# imu.net
KiCad netlist of a schematic drawn in Altium Designer
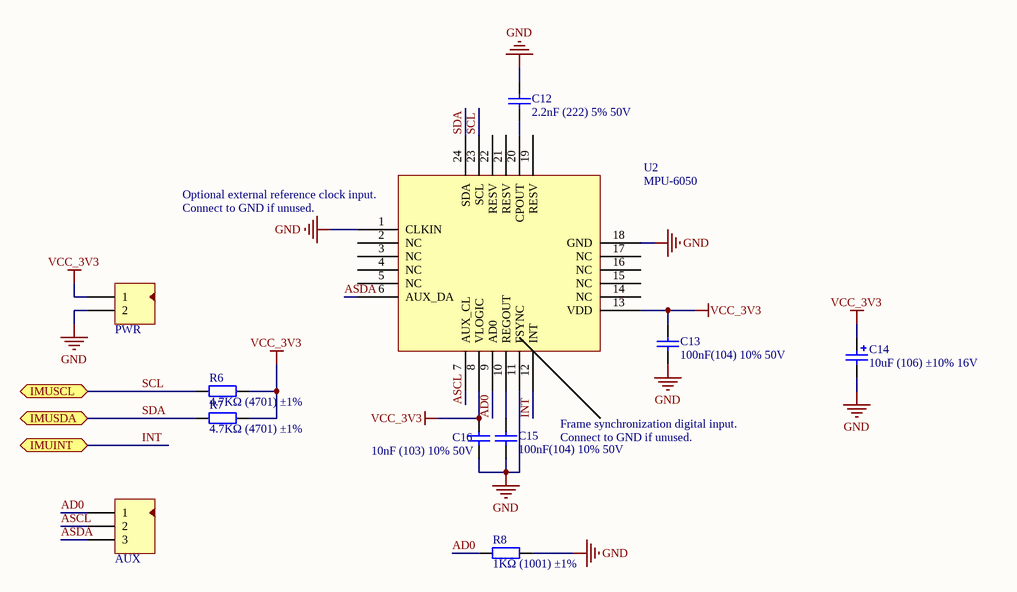
[diagram p0: imu.SchDoc]

(export (version "E")
  (design (tool "Eeschema 10.0.6"))
  (components
    (comp (ref "C12")
      (value "2.2nF (222) 5% 50V")
      (footprint "LC-0805_C")
      (description "贴片电容")
      (libsource (lib "Miscellaneous Devices LC") (part "0805 2.2nF (222) 5% 50V"))
    )
    (comp (ref "C13")
      (value "100nF(104) 10% 50V")
      (footprint "LC-0805_C")
      (description "贴片电容")
      (libsource (lib "Miscellaneous Devices LC") (part "0805 100nF(104) 10% 50V"))
    )
    (comp (ref "C14")
      (value "10uF (106) ±10% 16V")
      (footprint "LC-CASE-A_3216")
      (description "钽电容")
      (libsource (lib "Miscellaneous Devices LC") (part "3216 10uF (106) 10% 16V"))
    )
    (comp (ref "C15")
      (value "100nF(104) 10% 50V")
      (footprint "LC-0805_C")
      (description "贴片电容")
      (libsource (lib "Miscellaneous Devices LC") (part "0805 100nF(104) 10% 50V"))
    )
    (comp (ref "C16")
      (value "10nF (103) 10% 50V")
      (footprint "LC-0805_C")
      (description "贴片电容")
      (libsource (lib "Miscellaneous Devices LC") (part "0805 10nF (103) 10% 50V"))
    )
    (comp (ref "P6")
      (value "PWR")
      (footprint "HDR2X1-2.54")
      (description "接插件")
      (fields (field (name "PUBLISHER") "Altium Limited"))
      (libsource (lib "HDR_Fszhang") (part "Header 2"))
    )
    (comp (ref "P7")
      (value "AUX")
      (footprint "HDR3X1-2.54")
      (description "接插件")
      (fields (field (name "PUBLISHER") "Altium Limited"))
      (libsource (lib "HDR_Fszhang") (part "Header 3"))
    )
    (comp (ref "R6")
      (value "4.7KΩ (4701) ±1%")
      (footprint "LC-0805_R")
      (description "贴片电阻")
      (libsource (lib "Miscellaneous Devices LC") (part "0805 4.7KΩ (4701) 1%"))
    )
    (comp (ref "R7")
      (value "4.7KΩ (4701) ±1%")
      (footprint "LC-0805_R")
      (description "贴片电阻")
      (libsource (lib "Miscellaneous Devices LC") (part "0805 4.7KΩ (4701) 1%"))
    )
    (comp (ref "R8")
      (value "1KΩ (1001) ±1%")
      (footprint "LC-0805_R")
      (description "贴片电阻")
      (libsource (lib "Miscellaneous Devices LC") (part "0805 1KΩ (1001) 1%"))
    )
    (comp (ref "U2")
      (value "MPU-6050")
      (footprint "LC-QFN-24_4x4x05P")
      (description "传感器")
      (libsource (lib "Miscellaneous Devices LC") (part "MPU-6050"))
    )
  )
  (nets
    (net (code "1") (name "/AD0") (class "Default")
      (node (ref "P7") (pin "1") (pinfunction "1_1") (pintype "passive"))
      (node (ref "R8") (pin "1") (pinfunction "1_1") (pintype "passive"))
      (node (ref "U2") (pin "9") (pinfunction "AD0_9") (pintype "passive"))
    )
    (net (code "2") (name "/ASCL") (class "Default")
      (node (ref "P7") (pin "2") (pinfunction "2_2") (pintype "passive"))
      (node (ref "U2") (pin "7") (pinfunction "AUX_CL_7") (pintype "passive"))
    )
    (net (code "3") (name "/ASDA") (class "Default")
      (node (ref "P7") (pin "3") (pinfunction "3_3") (pintype "passive"))
      (node (ref "U2") (pin "6") (pinfunction "AUX_DA_6") (pintype "passive"))
    )
    (net (code "4") (name "/INT") (class "Default")
      (node (ref "U2") (pin "12") (pinfunction "INT_12") (pintype "passive"))
    )
    (net (code "5") (name "/SCL") (class "Default")
      (node (ref "R6") (pin "1") (pinfunction "1_1") (pintype "passive"))
      (node (ref "U2") (pin "23") (pinfunction "SCL_23") (pintype "passive"))
    )
    (net (code "6") (name "/SDA") (class "Default")
      (node (ref "R7") (pin "1") (pinfunction "1_1") (pintype "passive"))
      (node (ref "U2") (pin "24") (pinfunction "SDA_24") (pintype "passive"))
    )
    (net (code "7") (name "GND") (class "Default")
      (node (ref "C12") (pin "2") (pinfunction "2_2") (pintype "passive"))
      (node (ref "C13") (pin "1") (pinfunction "1_1") (pintype "passive"))
      (node (ref "C14") (pin "2") (pinfunction "2_2") (pintype "passive"))
      (node (ref "C15") (pin "2") (pinfunction "2_2") (pintype "passive"))
      (node (ref "C16") (pin "1") (pinfunction "1_1") (pintype "passive"))
      (node (ref "P6") (pin "2") (pinfunction "2_2") (pintype "passive"))
      (node (ref "R8") (pin "2") (pinfunction "2_2") (pintype "passive"))
      (node (ref "U2") (pin "1") (pinfunction "CLKIN_1") (pintype "passive"))
      (node (ref "U2") (pin "11") (pinfunction "FSYNC_11") (pintype "passive"))
      (node (ref "U2") (pin "18") (pinfunction "GND_18") (pintype "passive"))
    )
    (net (code "8") (name "Net-(U2-CPOUT)") (class "Default")
      (node (ref "C12") (pin "1") (pinfunction "1_1") (pintype "passive"))
      (node (ref "U2") (pin "20") (pinfunction "CPOUT_20") (pintype "passive"))
    )
    (net (code "9") (name "Net-(U2-REGOUT)") (class "Default")
      (node (ref "C15") (pin "1") (pinfunction "1_1") (pintype "passive"))
      (node (ref "U2") (pin "10") (pinfunction "REGOUT_10") (pintype "passive"))
    )
    (net (code "10") (name "VCC_3V3") (class "Default")
      (node (ref "C13") (pin "2") (pinfunction "2_2") (pintype "passive"))
      (node (ref "C14") (pin "1") (pinfunction "1_1") (pintype "passive"))
      (node (ref "C16") (pin "2") (pinfunction "2_2") (pintype "passive"))
      (node (ref "P6") (pin "1") (pinfunction "1_1") (pintype "passive"))
      (node (ref "R6") (pin "2") (pinfunction "2_2") (pintype "passive"))
      (node (ref "R7") (pin "2") (pinfunction "2_2") (pintype "passive"))
      (node (ref "U2") (pin "13") (pinfunction "VDD_13") (pintype "passive"))
      (node (ref "U2") (pin "8") (pinfunction "VLOGIC_8") (pintype "passive"))
    )
    (net (code "11") (name "unconnected-(U2-NC-Pad2)") (class "Default")
      (node (ref "U2") (pin "2") (pinfunction "NC_2") (pintype "passive"))
    )
    (net (code "12") (name "unconnected-(U2-NC-Pad3)") (class "Default")
      (node (ref "U2") (pin "3") (pinfunction "NC_3") (pintype "passive"))
    )
    (net (code "13") (name "unconnected-(U2-NC-Pad4)") (class "Default")
      (node (ref "U2") (pin "4") (pinfunction "NC_4") (pintype "passive"))
    )
    (net (code "14") (name "unconnected-(U2-NC-Pad5)") (class "Default")
      (node (ref "U2") (pin "5") (pinfunction "NC_5") (pintype "passive"))
    )
    (net (code "15") (name "unconnected-(U2-NC-Pad14)") (class "Default")
      (node (ref "U2") (pin "14") (pinfunction "NC_14") (pintype "passive"))
    )
    (net (code "16") (name "unconnected-(U2-NC-Pad15)") (class "Default")
      (node (ref "U2") (pin "15") (pinfunction "NC_15") (pintype "passive"))
    )
    (net (code "17") (name "unconnected-(U2-NC-Pad16)") (class "Default")
      (node (ref "U2") (pin "16") (pinfunction "NC_16") (pintype "passive"))
    )
    (net (code "18") (name "unconnected-(U2-NC-Pad17)") (class "Default")
      (node (ref "U2") (pin "17") (pinfunction "NC_17") (pintype "passive"))
    )
    (net (code "19") (name "unconnected-(U2-RESV-Pad19)") (class "Default")
      (node (ref "U2") (pin "19") (pinfunction "RESV_19") (pintype "passive"))
    )
    (net (code "20") (name "unconnected-(U2-RESV-Pad21)") (class "Default")
      (node (ref "U2") (pin "21") (pinfunction "RESV_21") (pintype "passive"))
    )
    (net (code "21") (name "unconnected-(U2-RESV-Pad22)") (class "Default")
      (node (ref "U2") (pin "22") (pinfunction "RESV_22") (pintype "passive"))
    )
  )
)
